# SCH_SrProj_v1_0.net
KiCad netlist of a schematic drawn in EasyEDA
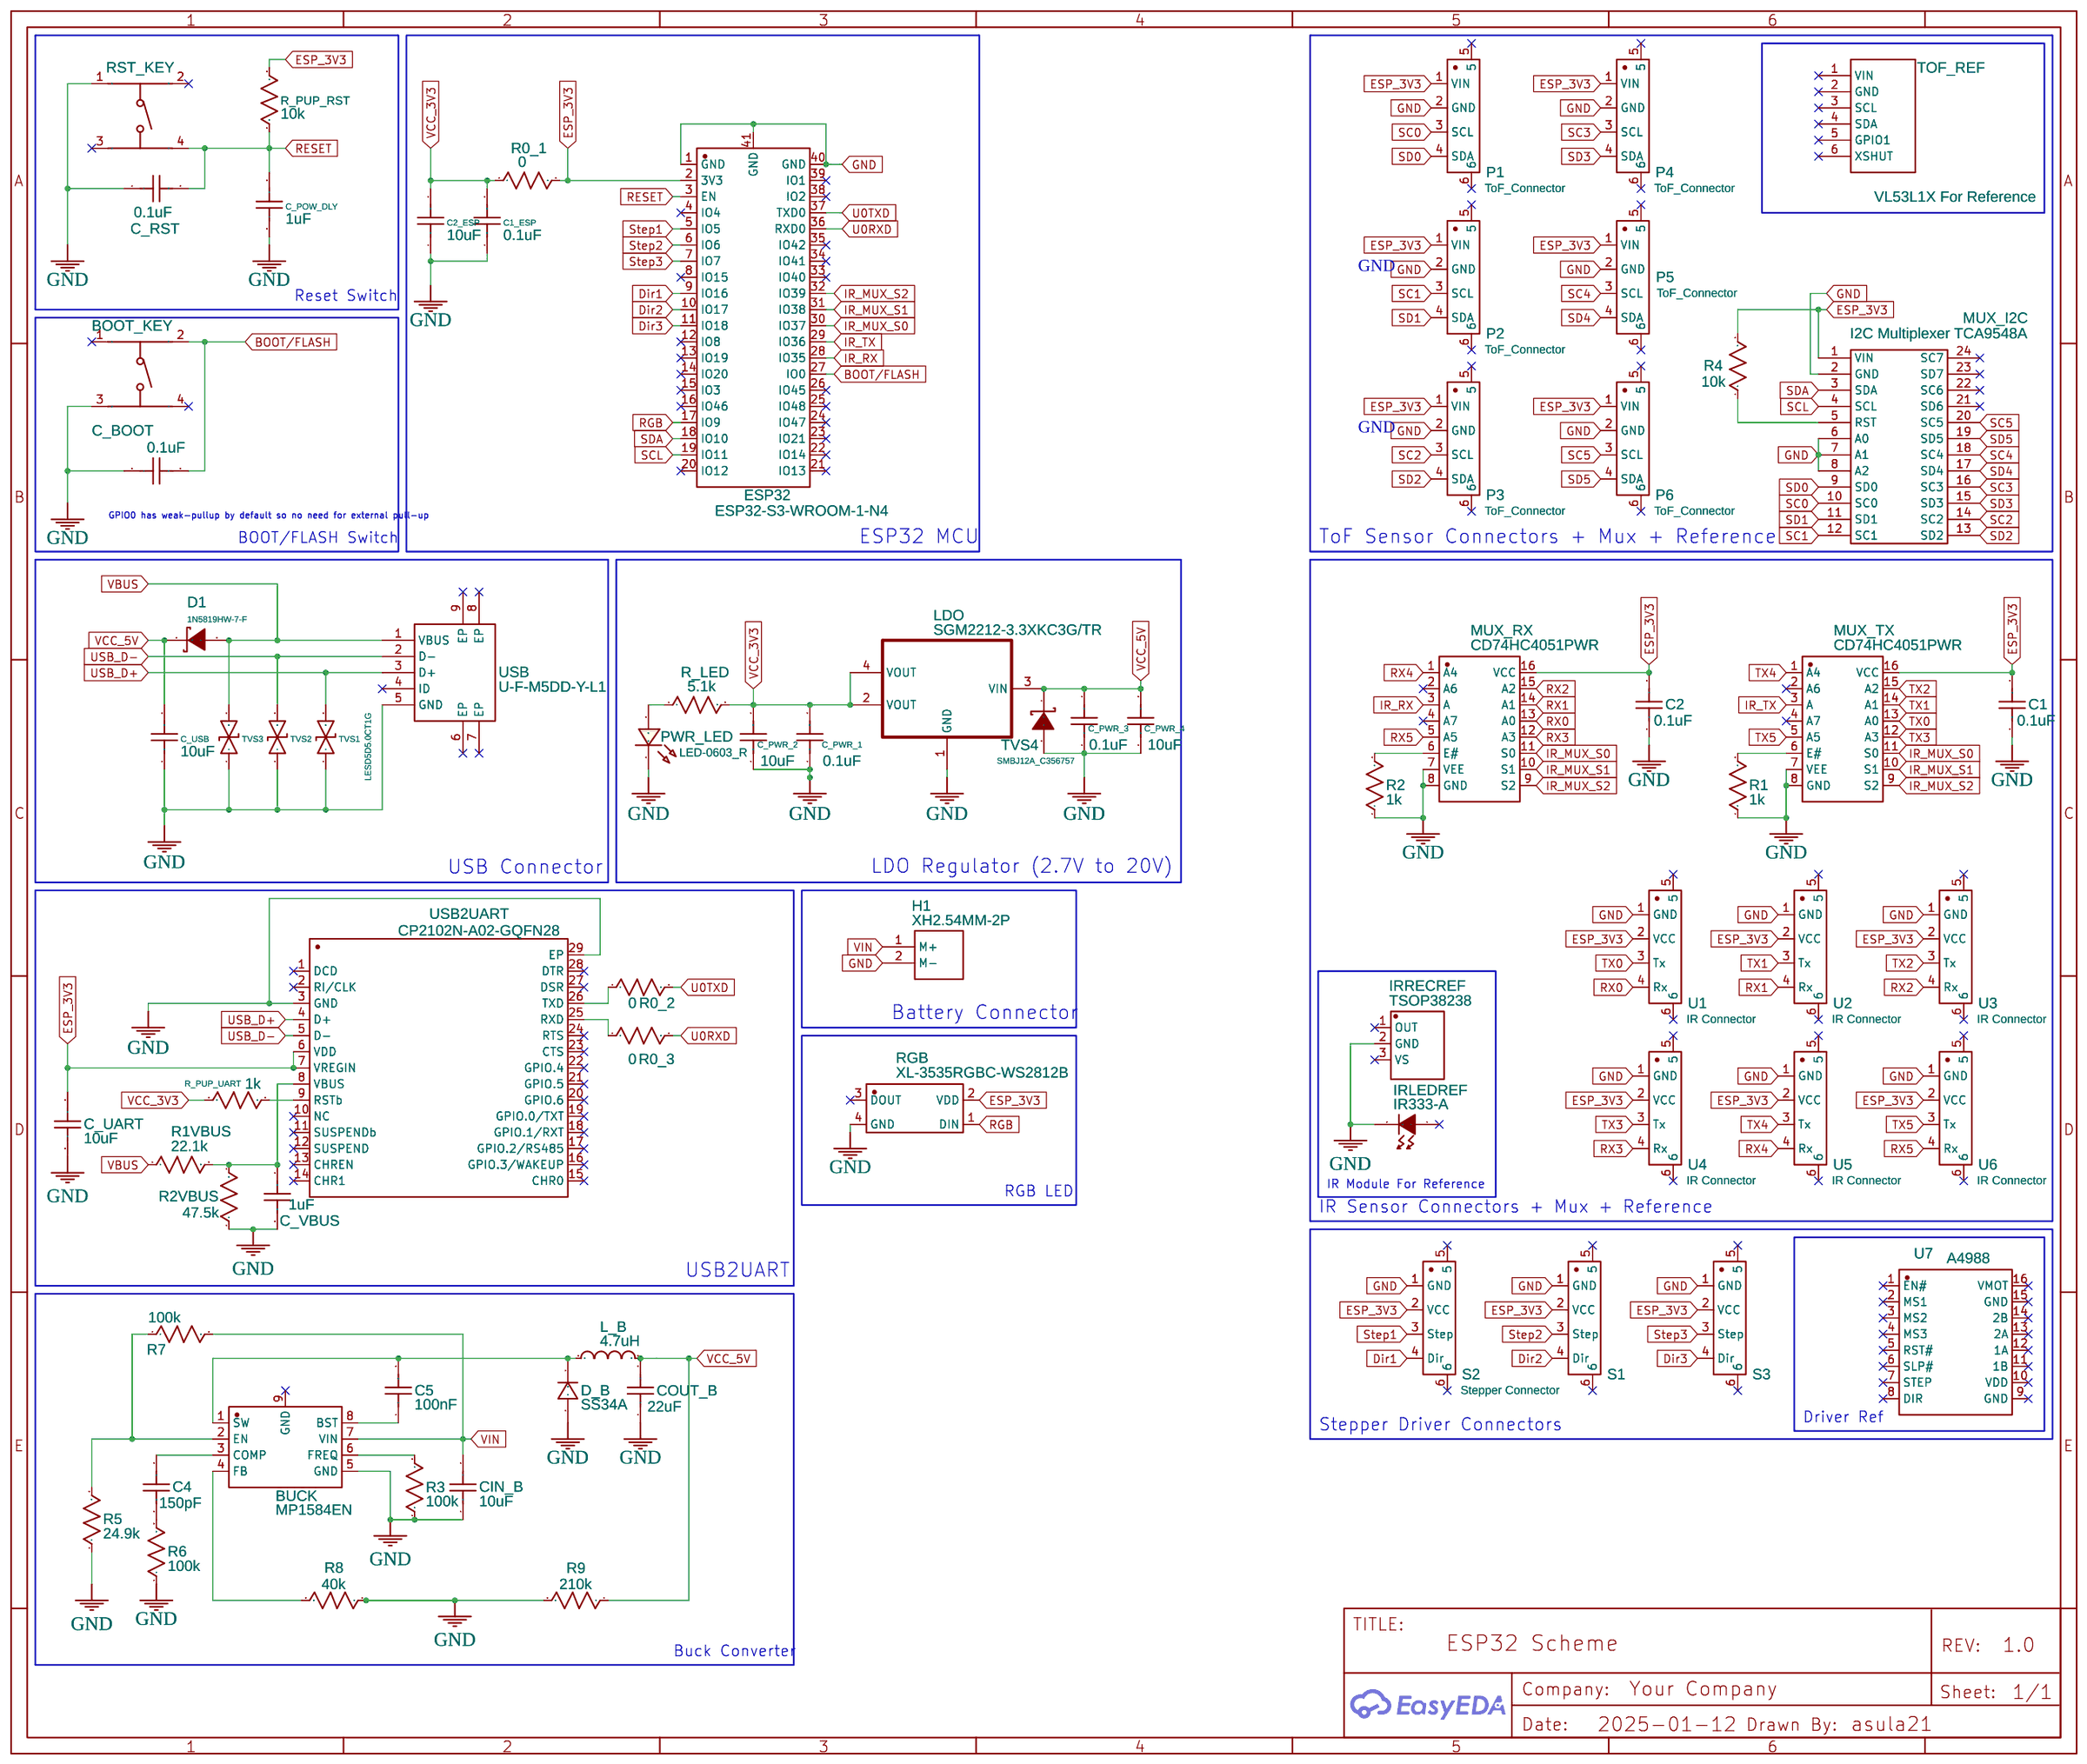
[diagram p0: schematic sheet]

(export (version "E")
  (design (tool "Eeschema 10.0.6"))
  (components
    (comp (ref "BOOT_KEY")
      (value "RSTBTN")
      (fields (field (name "Manufacturer Part") "BUTTON1"))
      (libsource (lib "") (part "BUTTON1"))
    )
    (comp (ref "BUCK") (value "MP1584EN") (libsource (lib "") (part "MP1584EN")))
    (comp (ref "C1") (value "0.1uF") (libsource (lib "") (part "C_0603_US_5")))
    (comp (ref "C1_ESP") (value "0.1uF") (libsource (lib "") (part "C_0603_US_7")))
    (comp (ref "C2") (value "0.1uF") (libsource (lib "") (part "C_0603_US_5")))
    (comp (ref "C2_ESP") (value "10uF") (libsource (lib "") (part "C_0603_US_4")))
    (comp (ref "C4") (value "150pF") (libsource (lib "") (part "C_0603_US_5")))
    (comp (ref "C5") (value "100nF") (libsource (lib "") (part "C_0603_US_5")))
    (comp (ref "CIN_B") (value "10uF") (libsource (lib "") (part "C_0603_US_6")))
    (comp (ref "COUT_B") (value "22uF") (libsource (lib "") (part "C_0603_US_11")))
    (comp (ref "C_BOOT") (value "0.1uF") (libsource (lib "") (part "C_0603_US_1")))
    (comp (ref "C_POW_DLY") (value "1uF") (libsource (lib "") (part "C_0603_US_2")))
    (comp (ref "C_PWR_1") (value "0.1uF") (libsource (lib "") (part "C_0603_US_3")))
    (comp (ref "C_PWR_2") (value "10uF") (libsource (lib "") (part "C_0603_US_3")))
    (comp (ref "C_PWR_3") (value "0.1uF") (libsource (lib "") (part "C_0603_US_3")))
    (comp (ref "C_PWR_4") (value "10uF") (libsource (lib "") (part "C_0603_US_3")))
    (comp (ref "C_RST") (value "0.1uF") (libsource (lib "") (part "C_0603_US")))
    (comp (ref "C_UART") (value "10uF") (libsource (lib "") (part "C_0603_US_8")))
    (comp (ref "C_USB") (value "10uF") (libsource (lib "") (part "C_0603_US_9")))
    (comp (ref "C_VBUS") (value "1uF") (libsource (lib "") (part "C_0603_US_10")))
    (comp (ref "D1")
      (value "1N5819HW-7-F")
      (fields (field (name "Manufacturer") "DIODES(美台)"))
      (libsource (lib "") (part "1N5819HW-7-F"))
    )
    (comp (ref "D_B")
      (value "SS34A")
      (fields (field (name "Manufacturer") "YANGJIE(扬杰)"))
      (libsource (lib "") (part "SS34A"))
    )
    (comp (ref "ESP32")
      (value "ESP32-S3-WROOM-1-N4")
      (fields (field (name "Manufacturer") "ESPRESSIF(乐鑫)"))
      (libsource (lib "") (part "ESP32-S3-WROOM-1-N4"))
    )
    (comp (ref "H1")
      (value "XH2.54MM-2P")
      (fields (field (name "Manufacturer Part") "Header P2 PH2.0 TUANLE"))
      (libsource (lib "") (part "PH2.0-2P"))
    )
    (comp (ref "IRLEDREF")
      (value "IR333-A")
      (fields (field (name "Manufacturer") "EVERLIGHT(亿光)"))
      (libsource (lib "") (part "IR333-A"))
    )
    (comp (ref "IRRECREF")
      (value "TSOP38238")
      (fields (field (name "Manufacturer") "VISHAY(威世)"))
      (libsource (lib "") (part "TSOP38238"))
    )
    (comp (ref "LDO") (value "SGM2212-3.3XKC3G/TR") (libsource (lib "") (part "SGM2212-3.3XKC3G/TR")))
    (comp (ref "L_B") (value "4.7uH") (libsource (lib "") (part "L0603_US")))
    (comp (ref "MUX_I2C")
      (value "I2C Multiplexer TCA9548A")
      (fields (field (name "Manufacturer Part") "IDSN-TCA9548A") (field (name "Manufacturer") "IDSN"))
      (libsource (lib "") (part "TCA9548A I2C MULTIPLEXER 8 CHANEL"))
    )
    (comp (ref "MUX_RX")
      (value "CD74HC4051PWR")
      (fields (field (name "Manufacturer") "TI(德州仪器)"))
      (libsource (lib "") (part "CD74HC4051PWR_1"))
    )
    (comp (ref "MUX_TX")
      (value "CD74HC4051PWR")
      (fields (field (name "Manufacturer") "TI(德州仪器)"))
      (libsource (lib "") (part "CD74HC4051PWR"))
    )
    (comp (ref "P1")
      (value "ToF_Connector")
      (fields (field (name "Manufacturer Part") "XH2.54MM-LI-4P"))
      (libsource (lib "") (part "XH2.54MM-LI-4P_1"))
    )
    (comp (ref "P2")
      (value "ToF_Connector")
      (fields (field (name "Manufacturer Part") "XH2.54MM-LI-4P"))
      (libsource (lib "") (part "XH2.54MM-LI-4P_1"))
    )
    (comp (ref "P3")
      (value "ToF_Connector")
      (fields (field (name "Manufacturer Part") "XH2.54MM-LI-4P"))
      (libsource (lib "") (part "XH2.54MM-LI-4P_1"))
    )
    (comp (ref "P4")
      (value "ToF_Connector")
      (fields (field (name "Manufacturer Part") "XH2.54MM-LI-4P"))
      (libsource (lib "") (part "XH2.54MM-LI-4P_1"))
    )
    (comp (ref "P5")
      (value "ToF_Connector")
      (fields (field (name "Manufacturer Part") "XH2.54MM-LI-4P"))
      (libsource (lib "") (part "XH2.54MM-LI-4P_1"))
    )
    (comp (ref "P6")
      (value "ToF_Connector")
      (fields (field (name "Manufacturer Part") "XH2.54MM-LI-4P"))
      (libsource (lib "") (part "XH2.54MM-LI-4P_1"))
    )
    (comp (ref "PWR_LED")
      (value "LED-0603_R")
      (fields
        (field (name "Manufacturer Part") "19-217/R6C-AL1M2VY/3T")
        (field (name "Manufacturer") "EVERLIGHT(台湾亿光)")
      )
      (libsource (lib "") (part "LED-0603_R"))
    )
    (comp (ref "R0_1") (value "0") (libsource (lib "") (part "R_0603_US_1")))
    (comp (ref "R0_2") (value "0") (libsource (lib "") (part "R_0603_US_1")))
    (comp (ref "R0_3") (value "0") (libsource (lib "") (part "R_0603_US_1")))
    (comp (ref "R1") (value "1k") (libsource (lib "") (part "R_0603_US")))
    (comp (ref "R1VBUS") (value "22.1k") (libsource (lib "") (part "R_0603_US_4")))
    (comp (ref "R2") (value "1k") (libsource (lib "") (part "R_0603_US")))
    (comp (ref "R2VBUS") (value "47.5k") (libsource (lib "") (part "R_0603_US_8")))
    (comp (ref "R3") (value "100k") (libsource (lib "") (part "R_0603_US")))
    (comp (ref "R4") (value "10k") (libsource (lib "") (part "R_0603_US")))
    (comp (ref "R5") (value "24.9k") (libsource (lib "") (part "R_0603_US")))
    (comp (ref "R6") (value "100k") (libsource (lib "") (part "R_0603_US")))
    (comp (ref "R7") (value "100k") (libsource (lib "") (part "R_0603_US_5")))
    (comp (ref "R8") (value "40k") (libsource (lib "") (part "R_0603_US_2")))
    (comp (ref "R9") (value "210k") (libsource (lib "") (part "R_0603_US_2")))
    (comp (ref "RGB")
      (value "XL-3535RGBC-WS2812B")
      (fields (field (name "Manufacturer") "XINGLIGHT(成兴光)"))
      (libsource (lib "") (part "XL-3535RGBC-WS2812B"))
    )
    (comp (ref "RST_KEY")
      (value "RSTBTN")
      (fields (field (name "Manufacturer Part") "BUTTON1"))
      (libsource (lib "") (part "BUTTON1_1"))
    )
    (comp (ref "R_LED") (value "5.1k") (libsource (lib "") (part "R_0603_US_7")))
    (comp (ref "R_PUP_RST") (value "10k") (libsource (lib "") (part "R_0603_US_6")))
    (comp (ref "R_PUP_UART") (value "1k") (libsource (lib "") (part "R_0603_US_3")))
    (comp (ref "S1")
      (value "Stepper Connector")
      (fields (field (name "Manufacturer Part") "XH2.54MM-LI-4P"))
      (libsource (lib "") (part "XH2.54MM-LI-4P_2"))
    )
    (comp (ref "S2")
      (value "Stepper Connector")
      (fields (field (name "Manufacturer Part") "XH2.54MM-LI-4P"))
      (libsource (lib "") (part "XH2.54MM-LI-4P_2"))
    )
    (comp (ref "S3")
      (value "Stepper Connector")
      (fields (field (name "Manufacturer Part") "XH2.54MM-LI-4P"))
      (libsource (lib "") (part "XH2.54MM-LI-4P_2"))
    )
    (comp (ref "TOF_REF")
      (value "VL53L1X For Reference")
      (fields (field (name "Manufacturer Part") "VL53L0X Time-of-Flight Distance Sensor VL53L0X"))
      (libsource (lib "") (part "VL53L1X_BREAKOUT"))
    )
    (comp (ref "TVS1")
      (value "LESD5D5.0CT1G")
      (fields (field (name "Manufacturer") "LRC(乐山无线电)"))
      (libsource (lib "") (part "LESD5D5.0CT1G"))
    )
    (comp (ref "TVS2")
      (value "LESD5D5.0CT1G")
      (fields (field (name "Manufacturer") "LRC(乐山无线电)"))
      (libsource (lib "") (part "LESD5D5.0CT1G"))
    )
    (comp (ref "TVS3")
      (value "LESD5D5.0CT1G")
      (fields (field (name "Manufacturer") "LRC(乐山无线电)"))
      (libsource (lib "") (part "LESD5D5.0CT1G"))
    )
    (comp (ref "TVS4")
      (value "SMBJ12A_C356757")
      (fields (field (name "Manufacturer Part") "SMBJ12A") (field (name "Manufacturer") "JJW(捷捷微)"))
      (libsource (lib "") (part "SMBJ12A_C356757"))
    )
    (comp (ref "U1")
      (value "IR Connector")
      (fields (field (name "Manufacturer Part") "XH2.54MM-LI-4P"))
      (libsource (lib "") (part "XH2.54MM-LI-4P"))
    )
    (comp (ref "U2")
      (value "IR Connector")
      (fields (field (name "Manufacturer Part") "XH2.54MM-LI-4P"))
      (libsource (lib "") (part "XH2.54MM-LI-4P"))
    )
    (comp (ref "U3")
      (value "IR Connector")
      (fields (field (name "Manufacturer Part") "XH2.54MM-LI-4P"))
      (libsource (lib "") (part "XH2.54MM-LI-4P"))
    )
    (comp (ref "U4")
      (value "IR Connector")
      (fields (field (name "Manufacturer Part") "XH2.54MM-LI-4P"))
      (libsource (lib "") (part "XH2.54MM-LI-4P"))
    )
    (comp (ref "U5")
      (value "IR Connector")
      (fields (field (name "Manufacturer Part") "XH2.54MM-LI-4P"))
      (libsource (lib "") (part "XH2.54MM-LI-4P"))
    )
    (comp (ref "U6")
      (value "IR Connector")
      (fields (field (name "Manufacturer Part") "XH2.54MM-LI-4P"))
      (libsource (lib "") (part "XH2.54MM-LI-4P"))
    )
    (comp (ref "U7") (value "A4988") (libsource (lib "") (part "A4988")))
    (comp (ref "USB")
      (value "U-F-M5DD-Y-L1")
      (fields (field (name "Manufacturer") "韩国韩荣"))
      (libsource (lib "") (part "U-F-M5DD-Y-L1"))
    )
    (comp (ref "USB2UART")
      (value "CP2102N-A02-GQFN28")
      (fields (field (name "Manufacturer") "SKYWORKS/SILICON LABS(芯科)"))
      (libsource (lib "") (part "CP2102N-A02-GQFN28"))
    )
  )
  (nets
    (net (code "1") (name "BOOT{slash}FLASH") (class "Default")
      (node (ref "BOOT_KEY") (pin "2") (pinfunction "2_2") (pintype "unspecified"))
      (node (ref "C_BOOT") (pin "2") (pinfunction "2_2") (pintype "unspecified"))
      (node (ref "ESP32") (pin "27") (pinfunction "IO0_27") (pintype "unspecified"))
    )
    (net (code "2") (name "Dir1") (class "Default")
      (node (ref "ESP32") (pin "9") (pinfunction "IO16_9") (pintype "unspecified"))
      (node (ref "S2") (pin "4") (pinfunction "Dir_4") (pintype "unspecified"))
    )
    (net (code "3") (name "Dir2") (class "Default")
      (node (ref "ESP32") (pin "10") (pinfunction "IO17_10") (pintype "unspecified"))
      (node (ref "S1") (pin "4") (pinfunction "Dir_4") (pintype "unspecified"))
    )
    (net (code "4") (name "Dir3") (class "Default")
      (node (ref "ESP32") (pin "11") (pinfunction "IO18_11") (pintype "unspecified"))
      (node (ref "S3") (pin "4") (pinfunction "Dir_4") (pintype "unspecified"))
    )
    (net (code "5") (name "ESP_3V3") (class "Default")
      (node (ref "C1") (pin "2") (pinfunction "2_2") (pintype "unspecified"))
      (node (ref "C2") (pin "2") (pinfunction "2_2") (pintype "unspecified"))
      (node (ref "C_UART") (pin "2") (pinfunction "2_2") (pintype "unspecified"))
      (node (ref "ESP32") (pin "2") (pinfunction "3V3_2") (pintype "unspecified"))
      (node (ref "MUX_I2C") (pin "1") (pinfunction "VIN_1") (pintype "unspecified"))
      (node (ref "MUX_RX") (pin "16") (pinfunction "VCC_16") (pintype "unspecified"))
      (node (ref "MUX_TX") (pin "16") (pinfunction "VCC_16") (pintype "unspecified"))
      (node (ref "P1") (pin "1") (pinfunction "VIN_1") (pintype "unspecified"))
      (node (ref "P2") (pin "1") (pinfunction "VIN_1") (pintype "unspecified"))
      (node (ref "P3") (pin "1") (pinfunction "VIN_1") (pintype "unspecified"))
      (node (ref "P4") (pin "1") (pinfunction "VIN_1") (pintype "unspecified"))
      (node (ref "P5") (pin "1") (pinfunction "VIN_1") (pintype "unspecified"))
      (node (ref "P6") (pin "1") (pinfunction "VIN_1") (pintype "unspecified"))
      (node (ref "R0_1") (pin "2") (pinfunction "2_2") (pintype "unspecified"))
      (node (ref "R4") (pin "2") (pinfunction "2_2") (pintype "unspecified"))
      (node (ref "RGB") (pin "2") (pinfunction "VDD_2") (pintype "unspecified"))
      (node (ref "R_PUP_RST") (pin "2") (pinfunction "2_2") (pintype "unspecified"))
      (node (ref "S1") (pin "2") (pinfunction "VCC_2") (pintype "unspecified"))
      (node (ref "S2") (pin "2") (pinfunction "VCC_2") (pintype "unspecified"))
      (node (ref "S3") (pin "2") (pinfunction "VCC_2") (pintype "unspecified"))
      (node (ref "U1") (pin "2") (pinfunction "VCC_2") (pintype "unspecified"))
      (node (ref "U2") (pin "2") (pinfunction "VCC_2") (pintype "unspecified"))
      (node (ref "U3") (pin "2") (pinfunction "VCC_2") (pintype "unspecified"))
      (node (ref "U4") (pin "2") (pinfunction "VCC_2") (pintype "unspecified"))
      (node (ref "U5") (pin "2") (pinfunction "VCC_2") (pintype "unspecified"))
      (node (ref "U6") (pin "2") (pinfunction "VCC_2") (pintype "unspecified"))
      (node (ref "USB2UART") (pin "6") (pinfunction "VDD_6") (pintype "unspecified"))
      (node (ref "USB2UART") (pin "7") (pinfunction "VREGIN_7") (pintype "unspecified"))
    )
    (net (code "6") (name "GND") (class "Default")
      (node (ref "BOOT_KEY") (pin "3") (pinfunction "3_3") (pintype "unspecified"))
      (node (ref "BUCK") (pin "5") (pinfunction "GND_5") (pintype "unspecified"))
      (node (ref "C1") (pin "1") (pinfunction "1_1") (pintype "unspecified"))
      (node (ref "C1_ESP") (pin "1") (pinfunction "1_1") (pintype "unspecified"))
      (node (ref "C2") (pin "1") (pinfunction "1_1") (pintype "unspecified"))
      (node (ref "C2_ESP") (pin "1") (pinfunction "1_1") (pintype "unspecified"))
      (node (ref "CIN_B") (pin "1") (pinfunction "1_1") (pintype "unspecified"))
      (node (ref "COUT_B") (pin "1") (pinfunction "1_1") (pintype "unspecified"))
      (node (ref "C_BOOT") (pin "1") (pinfunction "1_1") (pintype "unspecified"))
      (node (ref "C_POW_DLY") (pin "1") (pinfunction "1_1") (pintype "unspecified"))
      (node (ref "C_PWR_1") (pin "1") (pinfunction "1_1") (pintype "unspecified"))
      (node (ref "C_PWR_2") (pin "1") (pinfunction "1_1") (pintype "unspecified"))
      (node (ref "C_PWR_3") (pin "1") (pinfunction "1_1") (pintype "unspecified"))
      (node (ref "C_PWR_4") (pin "1") (pinfunction "1_1") (pintype "unspecified"))
      (node (ref "C_RST") (pin "1") (pinfunction "1_1") (pintype "unspecified"))
      (node (ref "C_UART") (pin "1") (pinfunction "1_1") (pintype "unspecified"))
      (node (ref "C_USB") (pin "1") (pinfunction "1_1") (pintype "unspecified"))
      (node (ref "C_VBUS") (pin "2") (pinfunction "2_2") (pintype "unspecified"))
      (node (ref "D_B") (pin "2") (pinfunction "A_2") (pintype "unspecified"))
      (node (ref "ESP32") (pin "1") (pinfunction "GND_1") (pintype "unspecified"))
      (node (ref "ESP32") (pin "40") (pinfunction "GND_40") (pintype "unspecified"))
      (node (ref "ESP32") (pin "41") (pinfunction "GND_41") (pintype "unspecified"))
      (node (ref "H1") (pin "2") (pinfunction "M-_2") (pintype "unspecified"))
      (node (ref "IRLEDREF") (pin "2") (pinfunction "C_2") (pintype "input"))
      (node (ref "IRRECREF") (pin "2") (pinfunction "GND_2") (pintype "unspecified"))
      (node (ref "LDO") (pin "1") (pinfunction "GND_1") (pintype "unspecified"))
      (node (ref "MUX_I2C") (pin "2") (pinfunction "GND_2") (pintype "unspecified"))
      (node (ref "MUX_I2C") (pin "6") (pinfunction "A0_6") (pintype "unspecified"))
      (node (ref "MUX_I2C") (pin "7") (pinfunction "A1_7") (pintype "unspecified"))
      (node (ref "MUX_I2C") (pin "8") (pinfunction "A2_8") (pintype "unspecified"))
      (node (ref "MUX_RX") (pin "7") (pinfunction "VEE_7") (pintype "unspecified"))
      (node (ref "MUX_RX") (pin "8") (pinfunction "GND_8") (pintype "unspecified"))
      (node (ref "MUX_TX") (pin "7") (pinfunction "VEE_7") (pintype "unspecified"))
      (node (ref "MUX_TX") (pin "8") (pinfunction "GND_8") (pintype "unspecified"))
      (node (ref "P1") (pin "2") (pinfunction "GND_2") (pintype "unspecified"))
      (node (ref "P2") (pin "2") (pinfunction "GND_2") (pintype "unspecified"))
      (node (ref "P3") (pin "2") (pinfunction "GND_2") (pintype "unspecified"))
      (node (ref "P4") (pin "2") (pinfunction "GND_2") (pintype "unspecified"))
      (node (ref "P5") (pin "2") (pinfunction "GND_2") (pintype "unspecified"))
      (node (ref "P6") (pin "2") (pinfunction "GND_2") (pintype "unspecified"))
      (node (ref "PWR_LED") (pin "2") (pinfunction "2_2") (pintype "unspecified"))
      (node (ref "R1") (pin "1") (pinfunction "1_1") (pintype "unspecified"))
      (node (ref "R2") (pin "1") (pinfunction "1_1") (pintype "unspecified"))
      (node (ref "R2VBUS") (pin "1") (pinfunction "1_1") (pintype "unspecified"))
      (node (ref "R3") (pin "1") (pinfunction "1_1") (pintype "unspecified"))
      (node (ref "R5") (pin "1") (pinfunction "1_1") (pintype "unspecified"))
      (node (ref "R6") (pin "1") (pinfunction "1_1") (pintype "unspecified"))
      (node (ref "R8") (pin "1") (pinfunction "1_1") (pintype "unspecified"))
      (node (ref "R9") (pin "2") (pinfunction "2_2") (pintype "unspecified"))
      (node (ref "RGB") (pin "4") (pinfunction "GND_4") (pintype "unspecified"))
      (node (ref "RST_KEY") (pin "1") (pinfunction "1_1") (pintype "unspecified"))
      (node (ref "S1") (pin "1") (pinfunction "GND_1") (pintype "unspecified"))
      (node (ref "S2") (pin "1") (pinfunction "GND_1") (pintype "unspecified"))
      (node (ref "S3") (pin "1") (pinfunction "GND_1") (pintype "unspecified"))
      (node (ref "TVS1") (pin "1") (pinfunction "1_1") (pintype "unspecified"))
      (node (ref "TVS2") (pin "1") (pinfunction "1_1") (pintype "unspecified"))
      (node (ref "TVS3") (pin "1") (pinfunction "1_1") (pintype "unspecified"))
      (node (ref "TVS4") (pin "2") (pinfunction "A_2") (pintype "unspecified"))
      (node (ref "U1") (pin "1") (pinfunction "GND_1") (pintype "unspecified"))
      (node (ref "U2") (pin "1") (pinfunction "GND_1") (pintype "unspecified"))
      (node (ref "U3") (pin "1") (pinfunction "GND_1") (pintype "unspecified"))
      (node (ref "U4") (pin "1") (pinfunction "GND_1") (pintype "unspecified"))
      (node (ref "U5") (pin "1") (pinfunction "GND_1") (pintype "unspecified"))
      (node (ref "U6") (pin "1") (pinfunction "GND_1") (pintype "unspecified"))
      (node (ref "USB") (pin "5") (pinfunction "GND_5") (pintype "unspecified"))
      (node (ref "USB2UART") (pin "29") (pinfunction "EP_29") (pintype "unspecified"))
      (node (ref "USB2UART") (pin "3") (pinfunction "GND_3") (pintype "unspecified"))
    )
    (net (code "7") (name "IR_MUX_S0") (class "Default")
      (node (ref "ESP32") (pin "30") (pinfunction "IO37_30") (pintype "unspecified"))
      (node (ref "MUX_RX") (pin "11") (pinfunction "S0_11") (pintype "unspecified"))
      (node (ref "MUX_TX") (pin "11") (pinfunction "S0_11") (pintype "unspecified"))
    )
    (net (code "8") (name "IR_MUX_S1") (class "Default")
      (node (ref "ESP32") (pin "31") (pinfunction "IO38_31") (pintype "unspecified"))
      (node (ref "MUX_RX") (pin "10") (pinfunction "S1_10") (pintype "unspecified"))
      (node (ref "MUX_TX") (pin "10") (pinfunction "S1_10") (pintype "unspecified"))
    )
    (net (code "9") (name "IR_MUX_S2") (class "Default")
      (node (ref "ESP32") (pin "32") (pinfunction "IO39_32") (pintype "unspecified"))
      (node (ref "MUX_RX") (pin "9") (pinfunction "S2_9") (pintype "unspecified"))
      (node (ref "MUX_TX") (pin "9") (pinfunction "S2_9") (pintype "unspecified"))
    )
    (net (code "10") (name "IR_RX") (class "Default")
      (node (ref "ESP32") (pin "28") (pinfunction "IO35_28") (pintype "unspecified"))
      (node (ref "MUX_RX") (pin "3") (pinfunction "A_3") (pintype "unspecified"))
    )
    (net (code "11") (name "IR_TX") (class "Default")
      (node (ref "ESP32") (pin "29") (pinfunction "IO36_29") (pintype "unspecified"))
      (node (ref "MUX_TX") (pin "3") (pinfunction "A_3") (pintype "unspecified"))
    )
    (net (code "12") (name "Net-(BUCK-BST)") (class "Default")
      (node (ref "BUCK") (pin "8") (pinfunction "BST_8") (pintype "unspecified"))
      (node (ref "C5") (pin "1") (pinfunction "1_1") (pintype "unspecified"))
    )
    (net (code "13") (name "Net-(BUCK-COMP)") (class "Default")
      (node (ref "BUCK") (pin "3") (pinfunction "COMP_3") (pintype "unspecified"))
      (node (ref "C4") (pin "2") (pinfunction "2_2") (pintype "unspecified"))
    )
    (net (code "14") (name "Net-(BUCK-EN)") (class "Default")
      (node (ref "BUCK") (pin "2") (pinfunction "EN_2") (pintype "unspecified"))
      (node (ref "R5") (pin "2") (pinfunction "2_2") (pintype "unspecified"))
      (node (ref "R7") (pin "1") (pinfunction "1_1") (pintype "unspecified"))
    )
    (net (code "15") (name "Net-(BUCK-FB)") (class "Default")
      (node (ref "BUCK") (pin "4") (pinfunction "FB_4") (pintype "unspecified"))
      (node (ref "R8") (pin "2") (pinfunction "2_2") (pintype "unspecified"))
    )
    (net (code "16") (name "Net-(BUCK-FREQ)") (class "Default")
      (node (ref "BUCK") (pin "6") (pinfunction "FREQ_6") (pintype "unspecified"))
      (node (ref "R3") (pin "2") (pinfunction "2_2") (pintype "unspecified"))
    )
    (net (code "17") (name "Net-(BUCK-SW)") (class "Default")
      (node (ref "BUCK") (pin "1") (pinfunction "SW_1") (pintype "unspecified"))
      (node (ref "C5") (pin "2") (pinfunction "2_2") (pintype "unspecified"))
      (node (ref "D_B") (pin "1") (pinfunction "C_1") (pintype "unspecified"))
      (node (ref "L_B") (pin "1") (pinfunction "1_1") (pintype "unspecified"))
    )
    (net (code "18") (name "Net-(C4-Pad1)") (class "Default")
      (node (ref "C4") (pin "1") (pinfunction "1_1") (pintype "unspecified"))
      (node (ref "R6") (pin "2") (pinfunction "2_2") (pintype "unspecified"))
    )
    (net (code "19") (name "Net-(MUX_I2C-RST)") (class "Default")
      (node (ref "MUX_I2C") (pin "5") (pinfunction "RST_5") (pintype "unspecified"))
      (node (ref "R4") (pin "1") (pinfunction "1_1") (pintype "unspecified"))
    )
    (net (code "20") (name "Net-(MUX_RX-E#)") (class "Default")
      (node (ref "MUX_RX") (pin "6") (pinfunction "E#_6") (pintype "unspecified"))
      (node (ref "R2") (pin "2") (pinfunction "2_2") (pintype "unspecified"))
    )
    (net (code "21") (name "Net-(MUX_TX-E#)") (class "Default")
      (node (ref "MUX_TX") (pin "6") (pinfunction "E#_6") (pintype "unspecified"))
      (node (ref "R1") (pin "2") (pinfunction "2_2") (pintype "unspecified"))
    )
    (net (code "22") (name "Net-(PWR_LED-Pad1)") (class "Default")
      (node (ref "PWR_LED") (pin "1") (pinfunction "1_1") (pintype "unspecified"))
      (node (ref "R_LED") (pin "1") (pinfunction "1_1") (pintype "unspecified"))
    )
    (net (code "23") (name "Net-(USB2UART-RSTb)") (class "Default")
      (node (ref "R_PUP_UART") (pin "1") (pinfunction "1_1") (pintype "unspecified"))
      (node (ref "USB2UART") (pin "9") (pinfunction "RSTb_9") (pintype "unspecified"))
    )
    (net (code "24") (name "Net-(USB2UART-RXD)") (class "Default")
      (node (ref "R0_3") (pin "1") (pinfunction "1_1") (pintype "unspecified"))
      (node (ref "USB2UART") (pin "25") (pinfunction "RXD_25") (pintype "unspecified"))
    )
    (net (code "25") (name "Net-(USB2UART-TXD)") (class "Default")
      (node (ref "R0_2") (pin "1") (pinfunction "1_1") (pintype "unspecified"))
      (node (ref "USB2UART") (pin "26") (pinfunction "TXD_26") (pintype "unspecified"))
    )
    (net (code "26") (name "Net-(USB2UART-VBUS)") (class "Default")
      (node (ref "C_VBUS") (pin "1") (pinfunction "1_1") (pintype "unspecified"))
      (node (ref "R1VBUS") (pin "2") (pinfunction "2_2") (pintype "unspecified"))
      (node (ref "R2VBUS") (pin "2") (pinfunction "2_2") (pintype "unspecified"))
      (node (ref "USB2UART") (pin "8") (pinfunction "VBUS_8") (pintype "unspecified"))
    )
    (net (code "27") (name "RESET") (class "Default")
      (node (ref "C_POW_DLY") (pin "2") (pinfunction "2_2") (pintype "unspecified"))
      (node (ref "C_RST") (pin "2") (pinfunction "2_2") (pintype "unspecified"))
      (node (ref "ESP32") (pin "3") (pinfunction "EN_3") (pintype "unspecified"))
      (node (ref "RST_KEY") (pin "4") (pinfunction "4_4") (pintype "unspecified"))
      (node (ref "R_PUP_RST") (pin "1") (pinfunction "1_1") (pintype "unspecified"))
    )
    (net (code "28") (name "RGB") (class "Default")
      (node (ref "ESP32") (pin "17") (pinfunction "IO9_17") (pintype "unspecified"))
      (node (ref "RGB") (pin "1") (pinfunction "DIN_1") (pintype "unspecified"))
    )
    (net (code "29") (name "RX0") (class "Default")
      (node (ref "MUX_RX") (pin "13") (pinfunction "A0_13") (pintype "unspecified"))
      (node (ref "U1") (pin "4") (pinfunction "Rx_4") (pintype "unspecified"))
    )
    (net (code "30") (name "RX1") (class "Default")
      (node (ref "MUX_RX") (pin "14") (pinfunction "A1_14") (pintype "unspecified"))
      (node (ref "U2") (pin "4") (pinfunction "Rx_4") (pintype "unspecified"))
    )
    (net (code "31") (name "RX2") (class "Default")
      (node (ref "MUX_RX") (pin "15") (pinfunction "A2_15") (pintype "unspecified"))
      (node (ref "U3") (pin "4") (pinfunction "Rx_4") (pintype "unspecified"))
    )
    (net (code "32") (name "RX3") (class "Default")
      (node (ref "MUX_RX") (pin "12") (pinfunction "A3_12") (pintype "unspecified"))
      (node (ref "U4") (pin "4") (pinfunction "Rx_4") (pintype "unspecified"))
    )
    (net (code "33") (name "RX4") (class "Default")
      (node (ref "MUX_RX") (pin "1") (pinfunction "A4_1") (pintype "unspecified"))
      (node (ref "U5") (pin "4") (pinfunction "Rx_4") (pintype "unspecified"))
    )
    (net (code "34") (name "RX5") (class "Default")
      (node (ref "MUX_RX") (pin "5") (pinfunction "A5_5") (pintype "unspecified"))
      (node (ref "U6") (pin "4") (pinfunction "Rx_4") (pintype "unspecified"))
    )
    (net (code "35") (name "SC0") (class "Default")
      (node (ref "MUX_I2C") (pin "10") (pinfunction "SC0_10") (pintype "unspecified"))
      (node (ref "P1") (pin "3") (pinfunction "SCL_3") (pintype "unspecified"))
    )
    (net (code "36") (name "SC1") (class "Default")
      (node (ref "MUX_I2C") (pin "12") (pinfunction "SC1_12") (pintype "unspecified"))
      (node (ref "P2") (pin "3") (pinfunction "SCL_3") (pintype "unspecified"))
    )
    (net (code "37") (name "SC2") (class "Default")
      (node (ref "MUX_I2C") (pin "14") (pinfunction "SC2_14") (pintype "unspecified"))
      (node (ref "P3") (pin "3") (pinfunction "SCL_3") (pintype "unspecified"))
    )
    (net (code "38") (name "SC3") (class "Default")
      (node (ref "MUX_I2C") (pin "16") (pinfunction "SC3_16") (pintype "unspecified"))
      (node (ref "P4") (pin "3") (pinfunction "SCL_3") (pintype "unspecified"))
    )
    (net (code "39") (name "SC4") (class "Default")
      (node (ref "MUX_I2C") (pin "18") (pinfunction "SC4_18") (pintype "unspecified"))
      (node (ref "P5") (pin "3") (pinfunction "SCL_3") (pintype "unspecified"))
    )
    (net (code "40") (name "SC5") (class "Default")
      (node (ref "MUX_I2C") (pin "20") (pinfunction "SC5_20") (pintype "unspecified"))
      (node (ref "P6") (pin "3") (pinfunction "SCL_3") (pintype "unspecified"))
    )
    (net (code "41") (name "SCL") (class "Default")
      (node (ref "ESP32") (pin "19") (pinfunction "IO11_19") (pintype "unspecified"))
      (node (ref "MUX_I2C") (pin "4") (pinfunction "SCL_4") (pintype "unspecified"))
    )
    (net (code "42") (name "SD0") (class "Default")
      (node (ref "MUX_I2C") (pin "9") (pinfunction "SD0_9") (pintype "unspecified"))
      (node (ref "P1") (pin "4") (pinfunction "SDA_4") (pintype "unspecified"))
    )
    (net (code "43") (name "SD1") (class "Default")
      (node (ref "MUX_I2C") (pin "11") (pinfunction "SD1_11") (pintype "unspecified"))
      (node (ref "P2") (pin "4") (pinfunction "SDA_4") (pintype "unspecified"))
    )
    (net (code "44") (name "SD2") (class "Default")
      (node (ref "MUX_I2C") (pin "13") (pinfunction "SD2_13") (pintype "unspecified"))
      (node (ref "P3") (pin "4") (pinfunction "SDA_4") (pintype "unspecified"))
    )
    (net (code "45") (name "SD3") (class "Default")
      (node (ref "MUX_I2C") (pin "15") (pinfunction "SD3_15") (pintype "unspecified"))
      (node (ref "P4") (pin "4") (pinfunction "SDA_4") (pintype "unspecified"))
    )
    (net (code "46") (name "SD4") (class "Default")
      (node (ref "MUX_I2C") (pin "17") (pinfunction "SD4_17") (pintype "unspecified"))
      (node (ref "P5") (pin "4") (pinfunction "SDA_4") (pintype "unspecified"))
    )
    (net (code "47") (name "SD5") (class "Default")
      (node (ref "MUX_I2C") (pin "19") (pinfunction "SD5_19") (pintype "unspecified"))
      (node (ref "P6") (pin "4") (pinfunction "SDA_4") (pintype "unspecified"))
    )
    (net (code "48") (name "SDA") (class "Default")
      (node (ref "ESP32") (pin "18") (pinfunction "IO10_18") (pintype "unspecified"))
      (node (ref "MUX_I2C") (pin "3") (pinfunction "SDA_3") (pintype "unspecified"))
    )
    (net (code "49") (name "Step1") (class "Default")
      (node (ref "ESP32") (pin "5") (pinfunction "IO5_5") (pintype "unspecified"))
      (node (ref "S2") (pin "3") (pinfunction "Step_3") (pintype "unspecified"))
    )
    (net (code "50") (name "Step2") (class "Default")
      (node (ref "ESP32") (pin "6") (pinfunction "IO6_6") (pintype "unspecified"))
      (node (ref "S1") (pin "3") (pinfunction "Step_3") (pintype "unspecified"))
    )
    (net (code "51") (name "Step3") (class "Default")
      (node (ref "ESP32") (pin "7") (pinfunction "IO7_7") (pintype "unspecified"))
      (node (ref "S3") (pin "3") (pinfunction "Step_3") (pintype "unspecified"))
    )
    (net (code "52") (name "TX0") (class "Default")
      (node (ref "MUX_TX") (pin "13") (pinfunction "A0_13") (pintype "unspecified"))
      (node (ref "U1") (pin "3") (pinfunction "Tx_3") (pintype "unspecified"))
    )
    (net (code "53") (name "TX1") (class "Default")
      (node (ref "MUX_TX") (pin "14") (pinfunction "A1_14") (pintype "unspecified"))
      (node (ref "U2") (pin "3") (pinfunction "Tx_3") (pintype "unspecified"))
    )
    (net (code "54") (name "TX2") (class "Default")
      (node (ref "MUX_TX") (pin "15") (pinfunction "A2_15") (pintype "unspecified"))
      (node (ref "U3") (pin "3") (pinfunction "Tx_3") (pintype "unspecified"))
    )
    (net (code "55") (name "TX3") (class "Default")
      (node (ref "MUX_TX") (pin "12") (pinfunction "A3_12") (pintype "unspecified"))
      (node (ref "U4") (pin "3") (pinfunction "Tx_3") (pintype "unspecified"))
    )
    (net (code "56") (name "TX4") (class "Default")
      (node (ref "MUX_TX") (pin "1") (pinfunction "A4_1") (pintype "unspecified"))
      (node (ref "U5") (pin "3") (pinfunction "Tx_3") (pintype "unspecified"))
    )
    (net (code "57") (name "TX5") (class "Default")
      (node (ref "MUX_TX") (pin "5") (pinfunction "A5_5") (pintype "unspecified"))
      (node (ref "U6") (pin "3") (pinfunction "Tx_3") (pintype "unspecified"))
    )
    (net (code "58") (name "U0RXD") (class "Default")
      (node (ref "ESP32") (pin "36") (pinfunction "RXD0_36") (pintype "unspecified"))
      (node (ref "R0_3") (pin "2") (pinfunction "2_2") (pintype "unspecified"))
    )
    (net (code "59") (name "U0TXD") (class "Default")
      (node (ref "ESP32") (pin "37") (pinfunction "TXD0_37") (pintype "unspecified"))
      (node (ref "R0_2") (pin "2") (pinfunction "2_2") (pintype "unspecified"))
    )
    (net (code "60") (name "USB_D+") (class "Default")
      (node (ref "TVS1") (pin "2") (pinfunction "2_2") (pintype "unspecified"))
      (node (ref "USB") (pin "3") (pinfunction "D+_3") (pintype "unspecified"))
      (node (ref "USB2UART") (pin "4") (pinfunction "D+_4") (pintype "unspecified"))
    )
    (net (code "61") (name "USB_D-") (class "Default")
      (node (ref "TVS2") (pin "2") (pinfunction "2_2") (pintype "unspecified"))
      (node (ref "USB") (pin "2") (pinfunction "D-_2") (pintype "unspecified"))
      (node (ref "USB2UART") (pin "5") (pinfunction "D-_5") (pintype "unspecified"))
    )
    (net (code "62") (name "VBUS") (class "Default")
      (node (ref "D1") (pin "2") (pinfunction "A_2") (pintype "unspecified"))
      (node (ref "R1VBUS") (pin "1") (pinfunction "1_1") (pintype "unspecified"))
      (node (ref "TVS3") (pin "2") (pinfunction "2_2") (pintype "unspecified"))
      (node (ref "USB") (pin "1") (pinfunction "VBUS_1") (pintype "unspecified"))
    )
    (net (code "63") (name "VCC_3V3") (class "Default")
      (node (ref "C1_ESP") (pin "2") (pinfunction "2_2") (pintype "unspecified"))
      (node (ref "C2_ESP") (pin "2") (pinfunction "2_2") (pintype "unspecified"))
      (node (ref "C_PWR_1") (pin "2") (pinfunction "2_2") (pintype "unspecified"))
      (node (ref "C_PWR_2") (pin "2") (pinfunction "2_2") (pintype "unspecified"))
      (node (ref "LDO") (pin "2") (pinfunction "VOUT_2") (pintype "unspecified"))
      (node (ref "LDO") (pin "4") (pinfunction "VOUT_4") (pintype "unspecified"))
      (node (ref "R0_1") (pin "1") (pinfunction "1_1") (pintype "unspecified"))
      (node (ref "R_LED") (pin "2") (pinfunction "2_2") (pintype "unspecified"))
      (node (ref "R_PUP_UART") (pin "2") (pinfunction "2_2") (pintype "unspecified"))
    )
    (net (code "64") (name "VCC_5V") (class "Default")
      (node (ref "COUT_B") (pin "2") (pinfunction "2_2") (pintype "unspecified"))
      (node (ref "C_PWR_3") (pin "2") (pinfunction "2_2") (pintype "unspecified"))
      (node (ref "C_PWR_4") (pin "2") (pinfunction "2_2") (pintype "unspecified"))
      (node (ref "C_USB") (pin "2") (pinfunction "2_2") (pintype "unspecified"))
      (node (ref "D1") (pin "1") (pinfunction "K_1") (pintype "unspecified"))
      (node (ref "LDO") (pin "3") (pinfunction "VIN_3") (pintype "unspecified"))
      (node (ref "L_B") (pin "2") (pinfunction "2_2") (pintype "unspecified"))
      (node (ref "R9") (pin "1") (pinfunction "1_1") (pintype "unspecified"))
      (node (ref "TVS4") (pin "1") (pinfunction "K_1") (pintype "unspecified"))
    )
    (net (code "65") (name "VIN") (class "Default")
      (node (ref "BUCK") (pin "7") (pinfunction "VIN_7") (pintype "unspecified"))
      (node (ref "CIN_B") (pin "2") (pinfunction "2_2") (pintype "unspecified"))
      (node (ref "H1") (pin "1") (pinfunction "M+_1") (pintype "unspecified"))
      (node (ref "R7") (pin "2") (pinfunction "2_2") (pintype "unspecified"))
    )
    (net (code "66") (name "unconnected-(BOOT_KEY-Pad1)") (class "Default")
      (node (ref "BOOT_KEY") (pin "1") (pinfunction "1_1") (pintype "unspecified+no_connect"))
    )
    (net (code "67") (name "unconnected-(BOOT_KEY-Pad4)") (class "Default")
      (node (ref "BOOT_KEY") (pin "4") (pinfunction "4_4") (pintype "unspecified+no_connect"))
    )
    (net (code "68") (name "unconnected-(BUCK-GND-Pad9)") (class "Default")
      (node (ref "BUCK") (pin "9") (pinfunction "GND_9") (pintype "unspecified+no_connect"))
    )
    (net (code "69") (name "unconnected-(ESP32-IO1-Pad39)") (class "Default")
      (node (ref "ESP32") (pin "39") (pinfunction "IO1_39") (pintype "unspecified+no_connect"))
    )
    (net (code "70") (name "unconnected-(ESP32-IO2-Pad38)") (class "Default")
      (node (ref "ESP32") (pin "38") (pinfunction "IO2_38") (pintype "unspecified+no_connect"))
    )
    (net (code "71") (name "unconnected-(ESP32-IO3-Pad15)") (class "Default")
      (node (ref "ESP32") (pin "15") (pinfunction "IO3_15") (pintype "unspecified+no_connect"))
    )
    (net (code "72") (name "unconnected-(ESP32-IO4-Pad4)") (class "Default")
      (node (ref "ESP32") (pin "4") (pinfunction "IO4_4") (pintype "unspecified+no_connect"))
    )
    (net (code "73") (name "unconnected-(ESP32-IO8-Pad12)") (class "Default")
      (node (ref "ESP32") (pin "12") (pinfunction "IO8_12") (pintype "unspecified+no_connect"))
    )
    (net (code "74") (name "unconnected-(ESP32-IO12-Pad20)") (class "Default")
      (node (ref "ESP32") (pin "20") (pinfunction "IO12_20") (pintype "unspecified+no_connect"))
    )
    (net (code "75") (name "unconnected-(ESP32-IO13-Pad21)") (class "Default")
      (node (ref "ESP32") (pin "21") (pinfunction "IO13_21") (pintype "unspecified+no_connect"))
    )
    (net (code "76") (name "unconnected-(ESP32-IO14-Pad22)") (class "Default")
      (node (ref "ESP32") (pin "22") (pinfunction "IO14_22") (pintype "unspecified+no_connect"))
    )
    (net (code "77") (name "unconnected-(ESP32-IO15-Pad8)") (class "Default")
      (node (ref "ESP32") (pin "8") (pinfunction "IO15_8") (pintype "unspecified+no_connect"))
    )
    (net (code "78") (name "unconnected-(ESP32-IO19-Pad13)") (class "Default")
      (node (ref "ESP32") (pin "13") (pinfunction "IO19_13") (pintype "unspecified+no_connect"))
    )
    (net (code "79") (name "unconnected-(ESP32-IO20-Pad14)") (class "Default")
      (node (ref "ESP32") (pin "14") (pinfunction "IO20_14") (pintype "unspecified+no_connect"))
    )
    (net (code "80") (name "unconnected-(ESP32-IO21-Pad23)") (class "Default")
      (node (ref "ESP32") (pin "23") (pinfunction "IO21_23") (pintype "unspecified+no_connect"))
    )
    (net (code "81") (name "unconnected-(ESP32-IO40-Pad33)") (class "Default")
      (node (ref "ESP32") (pin "33") (pinfunction "IO40_33") (pintype "unspecified+no_connect"))
    )
    (net (code "82") (name "unconnected-(ESP32-IO41-Pad34)") (class "Default")
      (node (ref "ESP32") (pin "34") (pinfunction "IO41_34") (pintype "unspecified+no_connect"))
    )
    (net (code "83") (name "unconnected-(ESP32-IO42-Pad35)") (class "Default")
      (node (ref "ESP32") (pin "35") (pinfunction "IO42_35") (pintype "unspecified+no_connect"))
    )
    (net (code "84") (name "unconnected-(ESP32-IO45-Pad26)") (class "Default")
      (node (ref "ESP32") (pin "26") (pinfunction "IO45_26") (pintype "unspecified+no_connect"))
    )
    (net (code "85") (name "unconnected-(ESP32-IO46-Pad16)") (class "Default")
      (node (ref "ESP32") (pin "16") (pinfunction "IO46_16") (pintype "unspecified+no_connect"))
    )
    (net (code "86") (name "unconnected-(ESP32-IO47-Pad24)") (class "Default")
      (node (ref "ESP32") (pin "24") (pinfunction "IO47_24") (pintype "unspecified+no_connect"))
    )
    (net (code "87") (name "unconnected-(ESP32-IO48-Pad25)") (class "Default")
      (node (ref "ESP32") (pin "25") (pinfunction "IO48_25") (pintype "unspecified+no_connect"))
    )
    (net (code "88") (name "unconnected-(IRLEDREF-A-Pad1)") (class "Default")
      (node (ref "IRLEDREF") (pin "1") (pinfunction "A_1") (pintype "input+no_connect"))
    )
    (net (code "89") (name "unconnected-(IRRECREF-OUT-Pad1)") (class "Default")
      (node (ref "IRRECREF") (pin "1") (pinfunction "OUT_1") (pintype "unspecified+no_connect"))
    )
    (net (code "90") (name "unconnected-(IRRECREF-VS-Pad3)") (class "Default")
      (node (ref "IRRECREF") (pin "3") (pinfunction "VS_3") (pintype "unspecified+no_connect"))
    )
    (net (code "91") (name "unconnected-(MUX_I2C-SC6-Pad22)") (class "Default")
      (node (ref "MUX_I2C") (pin "22") (pinfunction "SC6_22") (pintype "unspecified+no_connect"))
    )
    (net (code "92") (name "unconnected-(MUX_I2C-SC7-Pad24)") (class "Default")
      (node (ref "MUX_I2C") (pin "24") (pinfunction "SC7_24") (pintype "unspecified+no_connect"))
    )
    (net (code "93") (name "unconnected-(MUX_I2C-SD6-Pad21)") (class "Default")
      (node (ref "MUX_I2C") (pin "21") (pinfunction "SD6_21") (pintype "unspecified+no_connect"))
    )
    (net (code "94") (name "unconnected-(MUX_I2C-SD7-Pad23)") (class "Default")
      (node (ref "MUX_I2C") (pin "23") (pinfunction "SD7_23") (pintype "unspecified+no_connect"))
    )
    (net (code "95") (name "unconnected-(MUX_RX-A6-Pad2)") (class "Default")
      (node (ref "MUX_RX") (pin "2") (pinfunction "A6_2") (pintype "unspecified+no_connect"))
    )
    (net (code "96") (name "unconnected-(MUX_RX-A7-Pad4)") (class "Default")
      (node (ref "MUX_RX") (pin "4") (pinfunction "A7_4") (pintype "unspecified+no_connect"))
    )
    (net (code "97") (name "unconnected-(MUX_TX-A6-Pad2)") (class "Default")
      (node (ref "MUX_TX") (pin "2") (pinfunction "A6_2") (pintype "unspecified+no_connect"))
    )
    (net (code "98") (name "unconnected-(MUX_TX-A7-Pad4)") (class "Default")
      (node (ref "MUX_TX") (pin "4") (pinfunction "A7_4") (pintype "unspecified+no_connect"))
    )
    (net (code "99") (name "unconnected-(P1-Pad5)") (class "Default")
      (node (ref "P1") (pin "5") (pinfunction "5_5") (pintype "unspecified+no_connect"))
    )
    (net (code "100") (name "unconnected-(P1-Pad6)") (class "Default")
      (node (ref "P1") (pin "6") (pinfunction "6_6") (pintype "unspecified+no_connect"))
    )
    (net (code "101") (name "unconnected-(P2-Pad5)") (class "Default")
      (node (ref "P2") (pin "5") (pinfunction "5_5") (pintype "unspecified+no_connect"))
    )
    (net (code "102") (name "unconnected-(P2-Pad6)") (class "Default")
      (node (ref "P2") (pin "6") (pinfunction "6_6") (pintype "unspecified+no_connect"))
    )
    (net (code "103") (name "unconnected-(P3-Pad5)") (class "Default")
      (node (ref "P3") (pin "5") (pinfunction "5_5") (pintype "unspecified+no_connect"))
    )
    (net (code "104") (name "unconnected-(P3-Pad6)") (class "Default")
      (node (ref "P3") (pin "6") (pinfunction "6_6") (pintype "unspecified+no_connect"))
    )
    (net (code "105") (name "unconnected-(P4-Pad5)") (class "Default")
      (node (ref "P4") (pin "5") (pinfunction "5_5") (pintype "unspecified+no_connect"))
    )
    (net (code "106") (name "unconnected-(P4-Pad6)") (class "Default")
      (node (ref "P4") (pin "6") (pinfunction "6_6") (pintype "unspecified+no_connect"))
    )
    (net (code "107") (name "unconnected-(P5-Pad5)") (class "Default")
      (node (ref "P5") (pin "5") (pinfunction "5_5") (pintype "unspecified+no_connect"))
    )
    (net (code "108") (name "unconnected-(P5-Pad6)") (class "Default")
      (node (ref "P5") (pin "6") (pinfunction "6_6") (pintype "unspecified+no_connect"))
    )
    (net (code "109") (name "unconnected-(P6-Pad5)") (class "Default")
      (node (ref "P6") (pin "5") (pinfunction "5_5") (pintype "unspecified+no_connect"))
    )
    (net (code "110") (name "unconnected-(P6-Pad6)") (class "Default")
      (node (ref "P6") (pin "6") (pinfunction "6_6") (pintype "unspecified+no_connect"))
    )
    (net (code "111") (name "unconnected-(RGB-DOUT-Pad3)") (class "Default")
      (node (ref "RGB") (pin "3") (pinfunction "DOUT_3") (pintype "unspecified+no_connect"))
    )
    (net (code "112") (name "unconnected-(RST_KEY-Pad2)") (class "Default")
      (node (ref "RST_KEY") (pin "2") (pinfunction "2_2") (pintype "unspecified+no_connect"))
    )
    (net (code "113") (name "unconnected-(RST_KEY-Pad3)") (class "Default")
      (node (ref "RST_KEY") (pin "3") (pinfunction "3_3") (pintype "unspecified+no_connect"))
    )
    (net (code "114") (name "unconnected-(S1-Pad5)") (class "Default")
      (node (ref "S1") (pin "5") (pinfunction "5_5") (pintype "unspecified+no_connect"))
    )
    (net (code "115") (name "unconnected-(S1-Pad6)") (class "Default")
      (node (ref "S1") (pin "6") (pinfunction "6_6") (pintype "unspecified+no_connect"))
    )
    (net (code "116") (name "unconnected-(S2-Pad5)") (class "Default")
      (node (ref "S2") (pin "5") (pinfunction "5_5") (pintype "unspecified+no_connect"))
    )
    (net (code "117") (name "unconnected-(S2-Pad6)") (class "Default")
      (node (ref "S2") (pin "6") (pinfunction "6_6") (pintype "unspecified+no_connect"))
    )
    (net (code "118") (name "unconnected-(S3-Pad5)") (class "Default")
      (node (ref "S3") (pin "5") (pinfunction "5_5") (pintype "unspecified+no_connect"))
    )
    (net (code "119") (name "unconnected-(S3-Pad6)") (class "Default")
      (node (ref "S3") (pin "6") (pinfunction "6_6") (pintype "unspecified+no_connect"))
    )
    (net (code "120") (name "unconnected-(TOF_REF-GND-Pad2)") (class "Default")
      (node (ref "TOF_REF") (pin "2") (pinfunction "GND_2") (pintype "unspecified+no_connect"))
    )
    (net (code "121") (name "unconnected-(TOF_REF-GPIO1-Pad5)") (class "Default")
      (node (ref "TOF_REF") (pin "5") (pinfunction "GPIO1_5") (pintype "unspecified+no_connect"))
    )
    (net (code "122") (name "unconnected-(TOF_REF-SCL-Pad3)") (class "Default")
      (node (ref "TOF_REF") (pin "3") (pinfunction "SCL_3") (pintype "unspecified+no_connect"))
    )
    (net (code "123") (name "unconnected-(TOF_REF-SDA-Pad4)") (class "Default")
      (node (ref "TOF_REF") (pin "4") (pinfunction "SDA_4") (pintype "unspecified+no_connect"))
    )
    (net (code "124") (name "unconnected-(TOF_REF-VIN-Pad1)") (class "Default")
      (node (ref "TOF_REF") (pin "1") (pinfunction "VIN_1") (pintype "unspecified+no_connect"))
    )
    (net (code "125") (name "unconnected-(TOF_REF-XSHUT-Pad6)") (class "Default")
      (node (ref "TOF_REF") (pin "6") (pinfunction "XSHUT_6") (pintype "unspecified+no_connect"))
    )
    (net (code "126") (name "unconnected-(U1-Pad5)") (class "Default")
      (node (ref "U1") (pin "5") (pinfunction "5_5") (pintype "unspecified+no_connect"))
    )
    (net (code "127") (name "unconnected-(U1-Pad6)") (class "Default")
      (node (ref "U1") (pin "6") (pinfunction "6_6") (pintype "unspecified+no_connect"))
    )
    (net (code "128") (name "unconnected-(U2-Pad5)") (class "Default")
      (node (ref "U2") (pin "5") (pinfunction "5_5") (pintype "unspecified+no_connect"))
    )
    (net (code "129") (name "unconnected-(U2-Pad6)") (class "Default")
      (node (ref "U2") (pin "6") (pinfunction "6_6") (pintype "unspecified+no_connect"))
    )
    (net (code "130") (name "unconnected-(U3-Pad5)") (class "Default")
      (node (ref "U3") (pin "5") (pinfunction "5_5") (pintype "unspecified+no_connect"))
    )
    (net (code "131") (name "unconnected-(U3-Pad6)") (class "Default")
      (node (ref "U3") (pin "6") (pinfunction "6_6") (pintype "unspecified+no_connect"))
    )
    (net (code "132") (name "unconnected-(U4-Pad5)") (class "Default")
      (node (ref "U4") (pin "5") (pinfunction "5_5") (pintype "unspecified+no_connect"))
    )
    (net (code "133") (name "unconnected-(U4-Pad6)") (class "Default")
      (node (ref "U4") (pin "6") (pinfunction "6_6") (pintype "unspecified+no_connect"))
    )
    (net (code "134") (name "unconnected-(U5-Pad5)") (class "Default")
      (node (ref "U5") (pin "5") (pinfunction "5_5") (pintype "unspecified+no_connect"))
    )
    (net (code "135") (name "unconnected-(U5-Pad6)") (class "Default")
      (node (ref "U5") (pin "6") (pinfunction "6_6") (pintype "unspecified+no_connect"))
    )
    (net (code "136") (name "unconnected-(U6-Pad5)") (class "Default")
      (node (ref "U6") (pin "5") (pinfunction "5_5") (pintype "unspecified+no_connect"))
    )
    (net (code "137") (name "unconnected-(U6-Pad6)") (class "Default")
      (node (ref "U6") (pin "6") (pinfunction "6_6") (pintype "unspecified+no_connect"))
    )
    (net (code "138") (name "unconnected-(U7-1A-Pad12)") (class "Default")
      (node (ref "U7") (pin "12") (pinfunction "1A_12") (pintype "unspecified+no_connect"))
    )
    (net (code "139") (name "unconnected-(U7-1B-Pad11)") (class "Default")
      (node (ref "U7") (pin "11") (pinfunction "1B_11") (pintype "unspecified+no_connect"))
    )
    (net (code "140") (name "unconnected-(U7-2A-Pad13)") (class "Default")
      (node (ref "U7") (pin "13") (pinfunction "2A_13") (pintype "unspecified+no_connect"))
    )
    (net (code "141") (name "unconnected-(U7-2B-Pad14)") (class "Default")
      (node (ref "U7") (pin "14") (pinfunction "2B_14") (pintype "unspecified+no_connect"))
    )
    (net (code "142") (name "unconnected-(U7-DIR-Pad8)") (class "Default")
      (node (ref "U7") (pin "8") (pinfunction "DIR_8") (pintype "unspecified+no_connect"))
    )
    (net (code "143") (name "unconnected-(U7-EN#-Pad1)") (class "Default")
      (node (ref "U7") (pin "1") (pinfunction "EN#_1") (pintype "unspecified+no_connect"))
    )
    (net (code "144") (name "unconnected-(U7-GND-Pad9)") (class "Default")
      (node (ref "U7") (pin "9") (pinfunction "GND_9") (pintype "unspecified+no_connect"))
    )
    (net (code "145") (name "unconnected-(U7-GND-Pad15)") (class "Default")
      (node (ref "U7") (pin "15") (pinfunction "GND_15") (pintype "unspecified+no_connect"))
    )
    (net (code "146") (name "unconnected-(U7-MS1-Pad2)") (class "Default")
      (node (ref "U7") (pin "2") (pinfunction "MS1_2") (pintype "unspecified+no_connect"))
    )
    (net (code "147") (name "unconnected-(U7-MS2-Pad3)") (class "Default")
      (node (ref "U7") (pin "3") (pinfunction "MS2_3") (pintype "unspecified+no_connect"))
    )
    (net (code "148") (name "unconnected-(U7-MS3-Pad4)") (class "Default")
      (node (ref "U7") (pin "4") (pinfunction "MS3_4") (pintype "unspecified+no_connect"))
    )
    (net (code "149") (name "unconnected-(U7-RST#-Pad5)") (class "Default")
      (node (ref "U7") (pin "5") (pinfunction "RST#_5") (pintype "unspecified+no_connect"))
    )
    (net (code "150") (name "unconnected-(U7-SLP#-Pad6)") (class "Default")
      (node (ref "U7") (pin "6") (pinfunction "SLP#_6") (pintype "unspecified+no_connect"))
    )
    (net (code "151") (name "unconnected-(U7-STEP-Pad7)") (class "Default")
      (node (ref "U7") (pin "7") (pinfunction "STEP_7") (pintype "unspecified+no_connect"))
    )
    (net (code "152") (name "unconnected-(U7-VDD-Pad10)") (class "Default")
      (node (ref "U7") (pin "10") (pinfunction "VDD_10") (pintype "unspecified+no_connect"))
    )
    (net (code "153") (name "unconnected-(U7-VMOT-Pad16)") (class "Default")
      (node (ref "U7") (pin "16") (pinfunction "VMOT_16") (pintype "unspecified+no_connect"))
    )
    (net (code "154") (name "unconnected-(USB-EP-Pad6)") (class "Default")
      (node (ref "USB") (pin "6") (pinfunction "EP_6") (pintype "unspecified+no_connect"))
    )
    (net (code "155") (name "unconnected-(USB-EP-Pad7)") (class "Default")
      (node (ref "USB") (pin "7") (pinfunction "EP_7") (pintype "unspecified+no_connect"))
    )
    (net (code "156") (name "unconnected-(USB-EP-Pad8)") (class "Default")
      (node (ref "USB") (pin "8") (pinfunction "EP_8") (pintype "unspecified+no_connect"))
    )
    (net (code "157") (name "unconnected-(USB-EP-Pad9)") (class "Default")
      (node (ref "USB") (pin "9") (pinfunction "EP_9") (pintype "unspecified+no_connect"))
    )
    (net (code "158") (name "unconnected-(USB-ID-Pad4)") (class "Default")
      (node (ref "USB") (pin "4") (pinfunction "ID_4") (pintype "unspecified+no_connect"))
    )
    (net (code "159") (name "unconnected-(USB2UART-CHR0-Pad15)") (class "Default")
      (node (ref "USB2UART") (pin "15") (pinfunction "CHR0_15") (pintype "unspecified+no_connect"))
    )
    (net (code "160") (name "unconnected-(USB2UART-CHR1-Pad14)") (class "Default")
      (node (ref "USB2UART") (pin "14") (pinfunction "CHR1_14") (pintype "unspecified+no_connect"))
    )
    (net (code "161") (name "unconnected-(USB2UART-CHREN-Pad13)") (class "Default")
      (node (ref "USB2UART") (pin "13") (pinfunction "CHREN_13") (pintype "unspecified+no_connect"))
    )
    (net (code "162") (name "unconnected-(USB2UART-CTS-Pad23)") (class "Default")
      (node (ref "USB2UART") (pin "23") (pinfunction "CTS_23") (pintype "unspecified+no_connect"))
    )
    (net (code "163") (name "unconnected-(USB2UART-DCD-Pad1)") (class "Default")
      (node (ref "USB2UART") (pin "1") (pinfunction "DCD_1") (pintype "unspecified+no_connect"))
    )
    (net (code "164") (name "unconnected-(USB2UART-DSR-Pad27)") (class "Default")
      (node (ref "USB2UART") (pin "27") (pinfunction "DSR_27") (pintype "unspecified+no_connect"))
    )
    (net (code "165") (name "unconnected-(USB2UART-DTR-Pad28)") (class "Default")
      (node (ref "USB2UART") (pin "28") (pinfunction "DTR_28") (pintype "unspecified+no_connect"))
    )
    (net (code "166") (name "unconnected-(USB2UART-GPIO.0{slash}TXT-Pad19)") (class "Default")
      (node (ref "USB2UART") (pin "19") (pinfunction "GPIO.0/TXT_19") (pintype "unspecified+no_connect"))
    )
    (net (code "167") (name "unconnected-(USB2UART-GPIO.1{slash}RXT-Pad18)") (class "Default")
      (node (ref "USB2UART") (pin "18") (pinfunction "GPIO.1/RXT_18") (pintype "unspecified+no_connect"))
    )
    (net (code "168") (name "unconnected-(USB2UART-GPIO.2{slash}RS485-Pad17)") (class "Default")
      (node (ref "USB2UART") (pin "17") (pinfunction "GPIO.2/RS485_17") (pintype "unspecified+no_connect"))
    )
    (net (code "169") (name "unconnected-(USB2UART-GPIO.3{slash}WAKEUP-Pad16)") (class "Default")
      (node (ref "USB2UART") (pin "16") (pinfunction "GPIO.3/WAKEUP_16") (pintype "unspecified+no_connect"))
    )
    (net (code "170") (name "unconnected-(USB2UART-GPIO.4-Pad22)") (class "Default")
      (node (ref "USB2UART") (pin "22") (pinfunction "GPIO.4_22") (pintype "unspecified+no_connect"))
    )
    (net (code "171") (name "unconnected-(USB2UART-GPIO.5-Pad21)") (class "Default")
      (node (ref "USB2UART") (pin "21") (pinfunction "GPIO.5_21") (pintype "unspecified+no_connect"))
    )
    (net (code "172") (name "unconnected-(USB2UART-GPIO.6-Pad20)") (class "Default")
      (node (ref "USB2UART") (pin "20") (pinfunction "GPIO.6_20") (pintype "unspecified+no_connect"))
    )
    (net (code "173") (name "unconnected-(USB2UART-NC-Pad10)") (class "Default")
      (node (ref "USB2UART") (pin "10") (pinfunction "NC_10") (pintype "unspecified+no_connect"))
    )
    (net (code "174") (name "unconnected-(USB2UART-RI{slash}CLK-Pad2)") (class "Default")
      (node (ref "USB2UART") (pin "2") (pinfunction "RI/CLK_2") (pintype "unspecified+no_connect"))
    )
    (net (code "175") (name "unconnected-(USB2UART-RTS-Pad24)") (class "Default")
      (node (ref "USB2UART") (pin "24") (pinfunction "RTS_24") (pintype "unspecified+no_connect"))
    )
    (net (code "176") (name "unconnected-(USB2UART-SUSPEND-Pad12)") (class "Default")
      (node (ref "USB2UART") (pin "12") (pinfunction "SUSPEND_12") (pintype "unspecified+no_connect"))
    )
    (net (code "177") (name "unconnected-(USB2UART-SUSPENDb-Pad11)") (class "Default")
      (node (ref "USB2UART") (pin "11") (pinfunction "SUSPENDb_11") (pintype "unspecified+no_connect"))
    )
  )
)
